# fpga-bank8-outside.net
KiCad netlist of a schematic drawn in Altium Designer
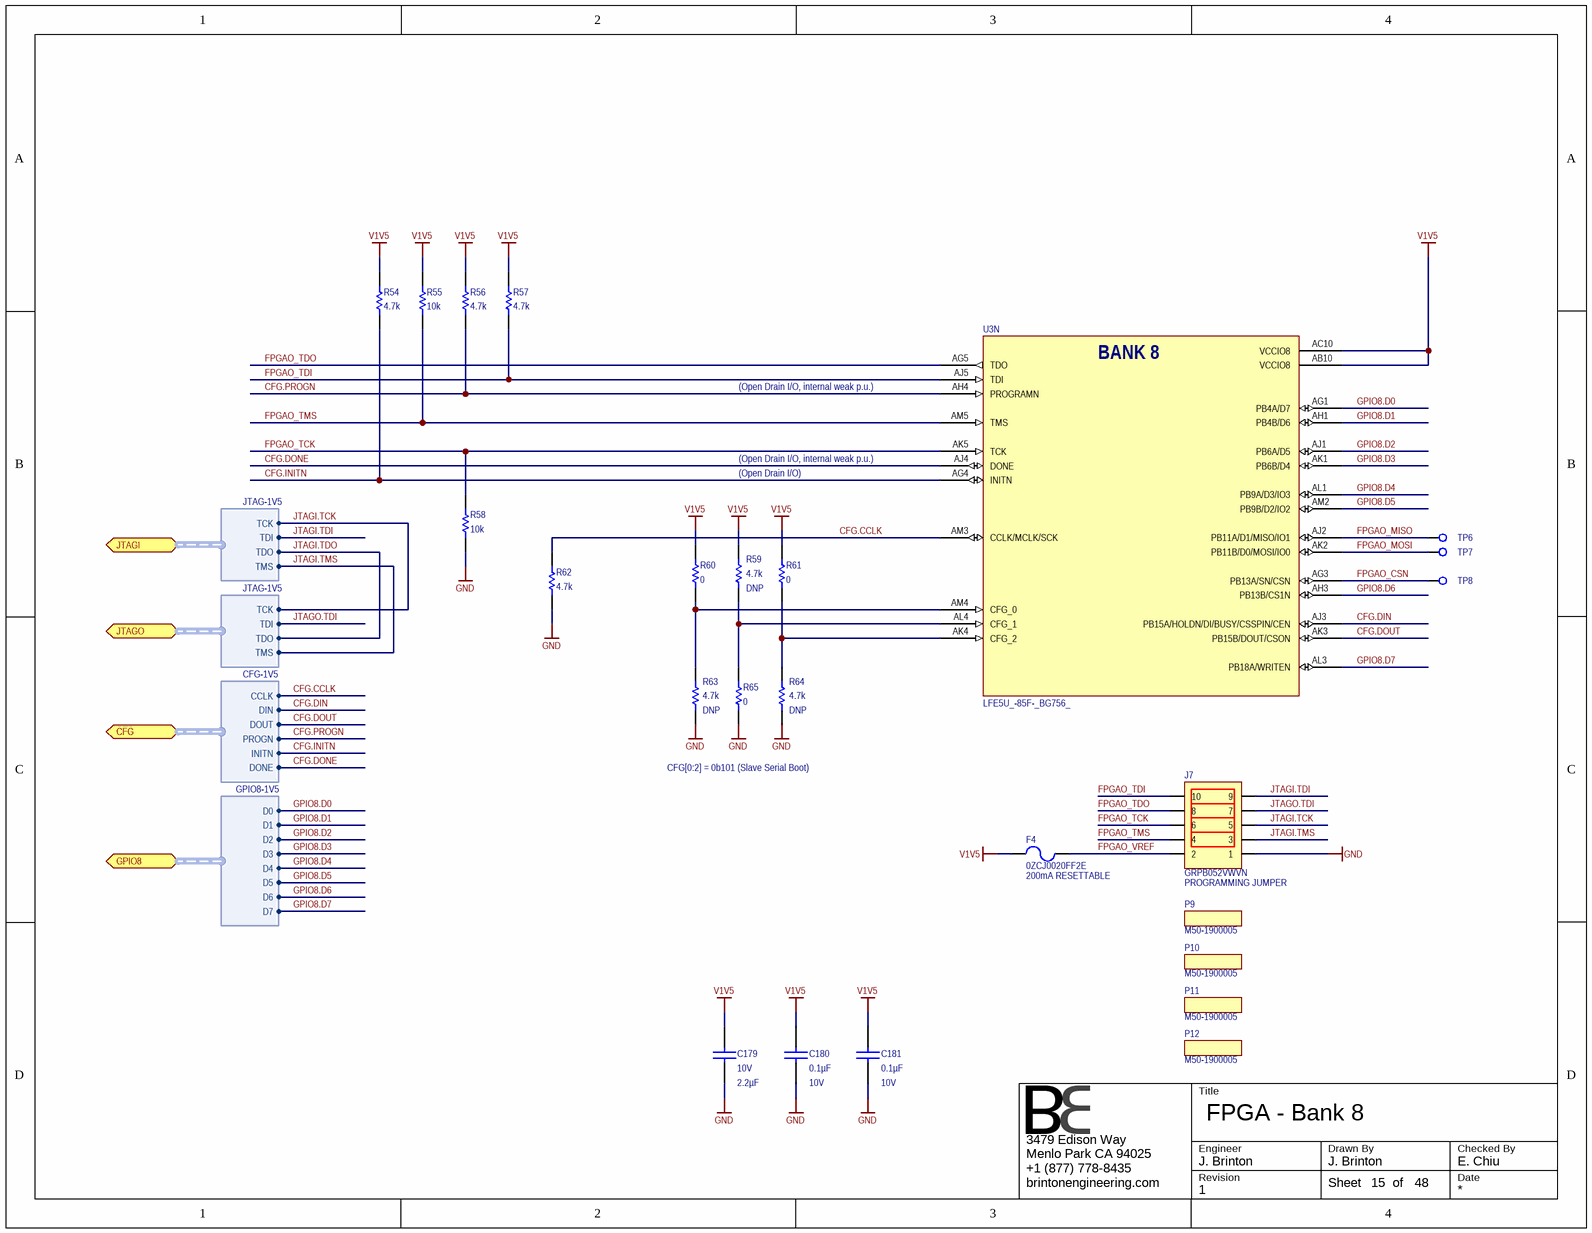
[diagram p0: fpga-bank8-outside.SchDoc]

(export (version "E")
  (design (tool "Eeschema 10.0.6"))
  (components
    (comp (ref "C179")
      (value "GRM188R71A225KE15D")
      (footprint "CAPC1608X90N")
      (description "CAP CER 2.2UF 10V 10% X7R 0603")
      (fields
        (field (name "MANUFACTURER") "Murata Electronics North America")
        (field (name "TOLERANCE") "±10%")
        (field (name "VOLTAGE - RATED") "10V")
        (field (name "CAPACITANCE") "2.2µF")
      )
      (libsource (lib "murata") (part "GRM188R71A225KE15D"))
    )
    (comp (ref "C180")
      (value "GRM155R71A104KA01J")
      (footprint "CAPC1005X56N")
      (description "CAP CER 0.1UF 10V 10% X7R 0402")
      (fields
        (field (name "MANUFACTURER") "Murata Electronics North America")
        (field (name "TOLERANCE") "±10%")
        (field (name "CAPACITANCE") "0.1µF")
        (field (name "VOLTAGE - RATED") "10V")
      )
      (libsource (lib "murata") (part "GRM155R71A104KA01J"))
    )
    (comp (ref "C181")
      (value "GRM155R71A104KA01J")
      (footprint "CAPC1005X56N")
      (description "CAP CER 0.1UF 10V 10% X7R 0402")
      (fields
        (field (name "MANUFACTURER") "Murata Electronics North America")
        (field (name "TOLERANCE") "±10%")
        (field (name "CAPACITANCE") "0.1µF")
        (field (name "VOLTAGE - RATED") "10V")
      )
      (libsource (lib "murata") (part "GRM155R71A104KA01J"))
    )
    (comp (ref "F4")
      (value "0ZCJ0020FF2E")
      (footprint "generic:1206")
      (description "PTC Resettable Fuse, 0.2A, 30V, SMD 1206")
      (fields (field (name "MANUFACTURER") "Bell Fuse"))
      (libsource (lib "bel-fuse") (part "0ZCJ0020FF2E"))
    )
    (comp (ref "J7")
      (value "GRPB052VWVN")
      (footprint "sullins:GRPB052VWVN")
      (description "Male Header, 0.050\" Pitch, 2x5 Position")
      (fields (field (name "MANUFACTURER") "Sullins"))
      (libsource (lib "sullins") (part "GRPB052VWVN"))
    )
    (comp (ref "P9")
      (value "M50-1900005")
      (description "1.27mm Jumper Socket")
      (fields (field (name "MANUFACTURER") "Harwin"))
      (libsource (lib "harwin") (part "M50-1900005"))
    )
    (comp (ref "P10")
      (value "M50-1900005")
      (description "1.27mm Jumper Socket")
      (fields (field (name "MANUFACTURER") "Harwin"))
      (libsource (lib "harwin") (part "M50-1900005"))
    )
    (comp (ref "P11")
      (value "M50-1900005")
      (description "1.27mm Jumper Socket")
      (fields (field (name "MANUFACTURER") "Harwin"))
      (libsource (lib "harwin") (part "M50-1900005"))
    )
    (comp (ref "P12")
      (value "M50-1900005")
      (description "1.27mm Jumper Socket")
      (fields (field (name "MANUFACTURER") "Harwin"))
      (libsource (lib "harwin") (part "M50-1900005"))
    )
    (comp (ref "R54")
      (value "4.7k")
      (footprint "0603")
      (description "Thick Film Resistor 4.7k Ohms +/-1% 0.1W 75V SMD 0603")
      (fields (field (name "TOLERANCE") "+/-1%") (field (name "MANUFACTURER") "Panasonic - ECG"))
      (libsource (lib "brinton") (part "RES"))
    )
    (comp (ref "R55")
      (value "10k")
      (footprint "0603")
      (description "Thick Film Resistor 10k Ohms +/-1% 0.1W SMD 0603")
      (fields (field (name "TOLERANCE") "+/-1%") (field (name "MANUFACTURER") "Panasonic - ECG"))
      (libsource (lib "brinton") (part "RES"))
    )
    (comp (ref "R56")
      (value "4.7k")
      (footprint "0603")
      (description "Thick Film Resistor 4.7k Ohms +/-1% 0.1W 75V SMD 0603")
      (fields (field (name "TOLERANCE") "+/-1%") (field (name "MANUFACTURER") "Panasonic - ECG"))
      (libsource (lib "brinton") (part "RES"))
    )
    (comp (ref "R57")
      (value "4.7k")
      (footprint "0603")
      (description "Thick Film Resistor 4.7k Ohms +/-1% 0.1W 75V SMD 0603")
      (fields (field (name "TOLERANCE") "+/-1%") (field (name "MANUFACTURER") "Panasonic - ECG"))
      (libsource (lib "brinton") (part "RES"))
    )
    (comp (ref "R58")
      (value "10k")
      (footprint "0603")
      (description "Thick Film Resistor 10k Ohms +/-1% 0.1W SMD 0603")
      (fields (field (name "TOLERANCE") "+/-1%") (field (name "MANUFACTURER") "Panasonic - ECG"))
      (libsource (lib "brinton") (part "RES"))
    )
    (comp (ref "R59")
      (value "4.7k")
      (footprint "0603")
      (description "Thick Film Resistor 4.7k Ohms +/-1% 0.1W 75V SMD 0603")
      (fields
        (field (name "TOLERANCE") "+/-1%")
        (field (name "MANUFACTURER") "Panasonic - ECG")
        (field (name "DO NOT PLACE") "DNP")
      )
      (libsource (lib "brinton") (part "RES"))
    )
    (comp (ref "R60")
      (value "0")
      (footprint "0603")
      (description "Thick Film Resistor 0 Ohms SMD 0603")
      (fields (field (name "TOLERANCE") "+/-1%") (field (name "MANUFACTURER") "Panasonic - ECG"))
      (libsource (lib "brinton") (part "RES"))
    )
    (comp (ref "R61")
      (value "0")
      (footprint "0603")
      (description "Thick Film Resistor 0 Ohms SMD 0603")
      (fields (field (name "TOLERANCE") "+/-1%") (field (name "MANUFACTURER") "Panasonic - ECG"))
      (libsource (lib "brinton") (part "RES"))
    )
    (comp (ref "R62")
      (value "4.7k")
      (footprint "0603")
      (description "Thick Film Resistor 4.7k Ohms +/-1% 0.1W 75V SMD 0603")
      (fields (field (name "TOLERANCE") "+/-1%") (field (name "MANUFACTURER") "Panasonic - ECG"))
      (libsource (lib "brinton") (part "RES"))
    )
    (comp (ref "R63")
      (value "4.7k")
      (footprint "0603")
      (description "Thick Film Resistor 4.7k Ohms +/-1% 0.1W 75V SMD 0603")
      (fields
        (field (name "TOLERANCE") "+/-1%")
        (field (name "MANUFACTURER") "Panasonic - ECG")
        (field (name "DO NOT PLACE") "DNP")
      )
      (libsource (lib "brinton") (part "RES"))
    )
    (comp (ref "R64")
      (value "4.7k")
      (footprint "0603")
      (description "Thick Film Resistor 4.7k Ohms +/-1% 0.1W 75V SMD 0603")
      (fields
        (field (name "TOLERANCE") "+/-1%")
        (field (name "MANUFACTURER") "Panasonic - ECG")
        (field (name "DO NOT PLACE") "DNP")
      )
      (libsource (lib "brinton") (part "RES"))
    )
    (comp (ref "R65")
      (value "0")
      (footprint "0603")
      (description "Thick Film Resistor 0 Ohms SMD 0603")
      (fields (field (name "TOLERANCE") "+/-1%") (field (name "MANUFACTURER") "Panasonic - ECG"))
      (libsource (lib "brinton") (part "RES"))
    )
    (comp (ref "TP6")
      (value "TEST_POINT_SMD_10")
      (footprint "generic:TEST_POINT_SMD_10")
      (description "Test Point SMD")
      (libsource (lib "generic") (part "TEST_POINT_SMD_10"))
    )
    (comp (ref "TP7")
      (value "TEST_POINT_SMD_10")
      (footprint "generic:TEST_POINT_SMD_10")
      (description "Test Point SMD")
      (libsource (lib "generic") (part "TEST_POINT_SMD_10"))
    )
    (comp (ref "TP8")
      (value "TEST_POINT_SMD_10")
      (footprint "generic:TEST_POINT_SMD_10")
      (description "Test Point SMD")
      (libsource (lib "generic") (part "TEST_POINT_SMD_10"))
    )
    (comp (ref "U3")
      (value "LFE5U_-85F-_BG756_")
      (footprint "lattice:caBGA756")
      (description "ECP5 FPGA, 85k LUT, 756-caBGA")
      (fields (field (name "MANUFACTURER") "Lattice Semiconductor"))
      (libsource (lib "lattice") (part "LFE5U_-85F-_BG756_"))
    )
  )
  (nets
    (net (code "4") (name "/CFG.CCLK") (class "Default")
      (node (ref "R62") (pin "2") (pinfunction "2_2") (pintype "passive"))
      (node (ref "U3") (pin "AM3") (pinfunction "CCLK/MCLK/SCK_AM3") (pintype "bidirectional"))
    )
    (net (code "5") (name "/CFG.DIN") (class "Default")
      (node (ref "U3") (pin "AJ3") (pinfunction "PB15A/HOLDN/DI/BUSY/CSSPIN/CEN_AJ3") (pintype "bidirectional"))
    )
    (net (code "6") (name "/CFG.DONE") (class "Default")
      (node (ref "U3") (pin "AJ4") (pinfunction "DONE_AJ4") (pintype "bidirectional"))
    )
    (net (code "7") (name "/CFG.DOUT") (class "Default")
      (node (ref "U3") (pin "AK3") (pinfunction "PB15B/DOUT/CSON_AK3") (pintype "bidirectional"))
    )
    (net (code "8") (name "/CFG.INITN") (class "Default")
      (node (ref "R54") (pin "1") (pinfunction "1_1") (pintype "passive"))
      (node (ref "U3") (pin "AG4") (pinfunction "INITN_AG4") (pintype "bidirectional"))
    )
    (net (code "9") (name "/CFG.PROGN") (class "Default")
      (node (ref "R56") (pin "1") (pinfunction "1_1") (pintype "passive"))
      (node (ref "U3") (pin "AH4") (pinfunction "PROGRAMN_AH4") (pintype "input"))
    )
    (net (code "10") (name "/FPGAO_CSN") (class "Default")
      (node (ref "TP8") (pin "1") (pinfunction "1_1") (pintype "passive"))
      (node (ref "U3") (pin "AG3") (pinfunction "PB13A/SN/CSN_AG3") (pintype "bidirectional"))
    )
    (net (code "11") (name "/FPGAO_MISO") (class "Default")
      (node (ref "TP6") (pin "1") (pinfunction "1_1") (pintype "passive"))
      (node (ref "U3") (pin "AJ2") (pinfunction "PB11A/D1/MISO/IO1_AJ2") (pintype "bidirectional"))
    )
    (net (code "12") (name "/FPGAO_MOSI") (class "Default")
      (node (ref "TP7") (pin "1") (pinfunction "1_1") (pintype "passive"))
      (node (ref "U3") (pin "AK2") (pinfunction "PB11B/D0/MOSI/IO0_AK2") (pintype "bidirectional"))
    )
    (net (code "13") (name "/FPGAO_TCK") (class "Default")
      (node (ref "J7") (pin "6") (pinfunction "6_6") (pintype "passive"))
      (node (ref "R58") (pin "2") (pinfunction "2_2") (pintype "passive"))
      (node (ref "U3") (pin "AK5") (pinfunction "TCK_AK5") (pintype "input"))
    )
    (net (code "14") (name "/FPGAO_TDI") (class "Default")
      (node (ref "J7") (pin "10") (pinfunction "10_10") (pintype "passive"))
      (node (ref "R57") (pin "1") (pinfunction "1_1") (pintype "passive"))
      (node (ref "U3") (pin "AJ5") (pinfunction "TDI_AJ5") (pintype "input"))
    )
    (net (code "15") (name "/FPGAO_TDO") (class "Default")
      (node (ref "J7") (pin "8") (pinfunction "8_8") (pintype "passive"))
      (node (ref "U3") (pin "AG5") (pinfunction "TDO_AG5") (pintype "output"))
    )
    (net (code "16") (name "/FPGAO_TMS") (class "Default")
      (node (ref "J7") (pin "4") (pinfunction "4_4") (pintype "passive"))
      (node (ref "R55") (pin "1") (pinfunction "1_1") (pintype "passive"))
      (node (ref "U3") (pin "AM5") (pinfunction "TMS_AM5") (pintype "input"))
    )
    (net (code "17") (name "/FPGAO_VREF") (class "Default")
      (node (ref "F4") (pin "2") (pinfunction "2_2") (pintype "passive"))
      (node (ref "J7") (pin "2") (pinfunction "2_2") (pintype "passive"))
    )
    (net (code "18") (name "/GPIO8.D0") (class "Default")
      (node (ref "U3") (pin "AG1") (pinfunction "PB4A/D7_AG1") (pintype "bidirectional"))
    )
    (net (code "19") (name "/GPIO8.D1") (class "Default")
      (node (ref "U3") (pin "AH1") (pinfunction "PB4B/D6_AH1") (pintype "bidirectional"))
    )
    (net (code "20") (name "/GPIO8.D2") (class "Default")
      (node (ref "U3") (pin "AJ1") (pinfunction "PB6A/D5_AJ1") (pintype "bidirectional"))
    )
    (net (code "21") (name "/GPIO8.D3") (class "Default")
      (node (ref "U3") (pin "AK1") (pinfunction "PB6B/D4_AK1") (pintype "bidirectional"))
    )
    (net (code "22") (name "/GPIO8.D4") (class "Default")
      (node (ref "U3") (pin "AL1") (pinfunction "PB9A/D3/IO3_AL1") (pintype "bidirectional"))
    )
    (net (code "23") (name "/GPIO8.D5") (class "Default")
      (node (ref "U3") (pin "AM2") (pinfunction "PB9B/D2/IO2_AM2") (pintype "bidirectional"))
    )
    (net (code "24") (name "/GPIO8.D6") (class "Default")
      (node (ref "U3") (pin "AH3") (pinfunction "PB13B/CS1N_AH3") (pintype "bidirectional"))
    )
    (net (code "25") (name "/GPIO8.D7") (class "Default")
      (node (ref "U3") (pin "AL3") (pinfunction "PB18A/WRITEN_AL3") (pintype "bidirectional"))
    )
    (net (code "26") (name "/JTAGI.TCK") (class "Default")
      (node (ref "J7") (pin "5") (pinfunction "5_5") (pintype "passive"))
    )
    (net (code "27") (name "/JTAGI.TDI") (class "Default")
      (node (ref "J7") (pin "9") (pinfunction "9_9") (pintype "passive"))
    )
    (net (code "29") (name "/JTAGI.TMS") (class "Default")
      (node (ref "J7") (pin "3") (pinfunction "3_3") (pintype "passive"))
    )
    (net (code "30") (name "/JTAGO.TDI") (class "Default")
      (node (ref "J7") (pin "7") (pinfunction "7_7") (pintype "passive"))
    )
    (net (code "34") (name "GND") (class "Default")
      (node (ref "C179") (pin "1") (pinfunction "1_1") (pintype "passive"))
      (node (ref "C180") (pin "1") (pinfunction "1_1") (pintype "passive"))
      (node (ref "C181") (pin "1") (pinfunction "1_1") (pintype "passive"))
      (node (ref "J7") (pin "1") (pinfunction "1_1") (pintype "passive"))
      (node (ref "R58") (pin "1") (pinfunction "1_1") (pintype "passive"))
      (node (ref "R62") (pin "1") (pinfunction "1_1") (pintype "passive"))
      (node (ref "R63") (pin "1") (pinfunction "1_1") (pintype "passive"))
      (node (ref "R64") (pin "1") (pinfunction "1_1") (pintype "passive"))
      (node (ref "R65") (pin "1") (pinfunction "1_1") (pintype "passive"))
    )
    (net (code "35") (name "Net-(U3N-CFG_0)") (class "Default")
      (node (ref "R60") (pin "1") (pinfunction "1_1") (pintype "passive"))
      (node (ref "R63") (pin "2") (pinfunction "2_2") (pintype "passive"))
      (node (ref "U3") (pin "AM4") (pinfunction "CFG_0_AM4") (pintype "input"))
    )
    (net (code "36") (name "Net-(U3N-CFG_1)") (class "Default")
      (node (ref "R59") (pin "1") (pinfunction "1_1") (pintype "passive"))
      (node (ref "R65") (pin "2") (pinfunction "2_2") (pintype "passive"))
      (node (ref "U3") (pin "AL4") (pinfunction "CFG_1_AL4") (pintype "input"))
    )
    (net (code "37") (name "Net-(U3N-CFG_2)") (class "Default")
      (node (ref "R61") (pin "1") (pinfunction "1_1") (pintype "passive"))
      (node (ref "R64") (pin "2") (pinfunction "2_2") (pintype "passive"))
      (node (ref "U3") (pin "AK4") (pinfunction "CFG_2_AK4") (pintype "input"))
    )
    (net (code "38") (name "V1V5") (class "Default")
      (node (ref "C179") (pin "2") (pinfunction "2_2") (pintype "passive"))
      (node (ref "C180") (pin "2") (pinfunction "2_2") (pintype "passive"))
      (node (ref "C181") (pin "2") (pinfunction "2_2") (pintype "passive"))
      (node (ref "F4") (pin "1") (pinfunction "1_1") (pintype "passive"))
      (node (ref "R54") (pin "2") (pinfunction "2_2") (pintype "passive"))
      (node (ref "R55") (pin "2") (pinfunction "2_2") (pintype "passive"))
      (node (ref "R56") (pin "2") (pinfunction "2_2") (pintype "passive"))
      (node (ref "R57") (pin "2") (pinfunction "2_2") (pintype "passive"))
      (node (ref "R59") (pin "2") (pinfunction "2_2") (pintype "passive"))
      (node (ref "R60") (pin "2") (pinfunction "2_2") (pintype "passive"))
      (node (ref "R61") (pin "2") (pinfunction "2_2") (pintype "passive"))
      (node (ref "U3") (pin "AB10") (pinfunction "VCCIO8_AB10") (pintype "power_in"))
      (node (ref "U3") (pin "AC10") (pinfunction "VCCIO8_AC10") (pintype "power_in"))
    )
  )
)
